# communication.net
KiCad netlist of a schematic drawn in Altium Designer
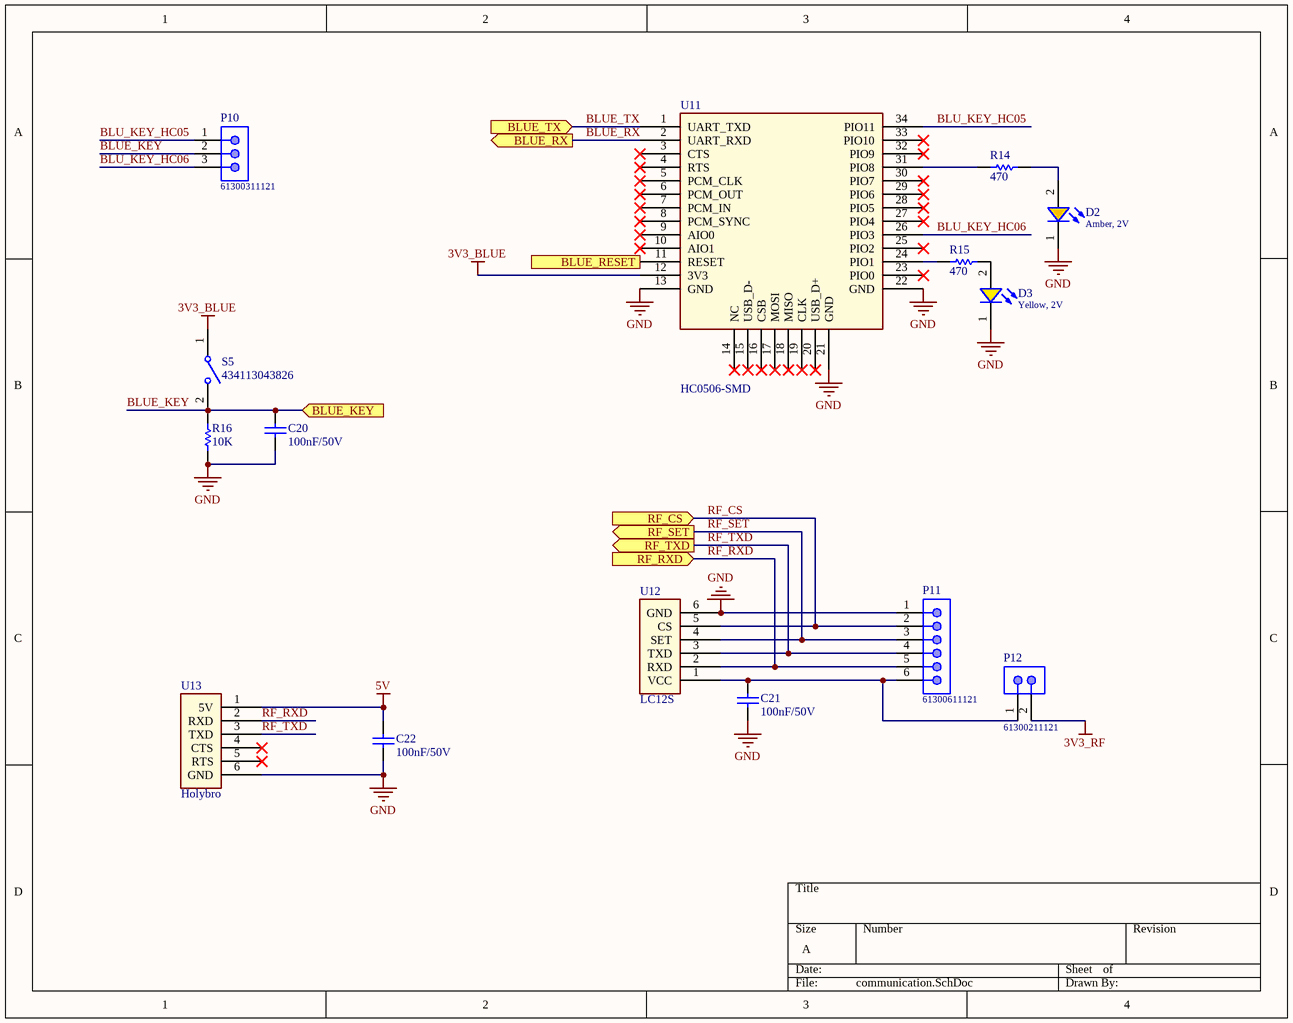
[diagram p0: communication.SchDoc]

(export (version "E")
  (design (tool "Eeschema 10.0.6"))
  (components
    (comp (ref "C20")
      (value "100nF/50V")
      (footprint "CAP-SM-0805")
      (description "CAP CER 0.1UF 50V Y5V 0805")
      (fields
        (field (name "MANUFACTURER") "Samsung Electro-Mechanics")
        (field (name "MANUFACTURER PART NUMBER") "CL21F104ZBCNNNC")
      )
      (libsource (lib "Capacitor") (part "Cap-100nF-50V-0805"))
    )
    (comp (ref "C21")
      (value "100nF/50V")
      (footprint "CAP-SM-0805")
      (description "CAP CER 0.1UF 50V Y5V 0805")
      (fields
        (field (name "MANUFACTURER") "Samsung Electro-Mechanics")
        (field (name "MANUFACTURER PART NUMBER") "CL21F104ZBCNNNC")
      )
      (libsource (lib "Capacitor") (part "Cap-100nF-50V-0805"))
    )
    (comp (ref "C22")
      (value "100nF/50V")
      (footprint "CAP-SM-0805")
      (description "CAP CER 0.1UF 50V Y5V 0805")
      (fields
        (field (name "MANUFACTURER") "Samsung Electro-Mechanics")
        (field (name "MANUFACTURER PART NUMBER") "CL21F104ZBCNNNC")
      )
      (libsource (lib "Capacitor") (part "Cap-100nF-50V-0805"))
    )
    (comp (ref "D2")
      (value "Amber, 2V")
      (footprint "WL-SMCW_0805")
      (description "WL-SMCW SMT Mono-color Chip LED Waterclear, size 0805, Amber, 2V, 140deg")
      (fields (field (name "PART NUMBER") "150080AS75000") (field (name "PUBLISHER") "Wurth Elektronik"))
      (libsource (lib "Chip_LEDs") (part "150080AS75000"))
    )
    (comp (ref "D3")
      (value "Yellow, 2V")
      (footprint "WL-SMCW_0805")
      (description "WL-SMCW SMT Mono-color Chip LED Waterclear, size 0805, Yellow, 2V, 140deg")
      (fields (field (name "PART NUMBER") "150080YS75000") (field (name "PUBLISHER") "Wurth Elektronik"))
      (libsource (lib "Chip_LEDs") (part "150080YS75000"))
    )
    (comp (ref "P10")
      (value "61300311121")
      (footprint "61300311121")
      (description "WR-PHD Pin Header, THT, pitch 2.54mm, Single Row, Vertical, 3p")
      (fields (field (name "MANUFACTURER") "Wurth Elektronik"))
      (libsource (lib "Pluggable_Connector") (part "61300311121"))
    )
    (comp (ref "P11")
      (value "61300611121")
      (footprint "61300611121")
      (description "WR-PHD Pin Header, THT, pitch 2.54mm, Single Row, Vertical, 6p")
      (fields (field (name "MANUFACTURER") "Wurth Elektronik"))
      (libsource (lib "Pluggable_Connector") (part "61300611121"))
    )
    (comp (ref "P12")
      (value "61300211121")
      (footprint "61300211121")
      (description "WR-PHD Pin Header, THT, pitch 2.54mm, Single Row, Vertical, 2p")
      (fields (field (name "MANUFACTURER") "Wurth Elektronik"))
      (libsource (lib "Pluggable_Connector") (part "61300211121"))
    )
    (comp (ref "R14")
      (value "470")
      (footprint "Resistor:RES-SM-0805")
      (description "RES 470 OHM JUMPER 0805")
      (fields
        (field (name "MANUFACTURER") "YAG6006CT-ND")
        (field (name "MANUFACTURER PART NUMBER") "PE0805FRF7W0R047L")
      )
      (libsource (lib "Resistor") (part "Res-470-0805"))
    )
    (comp (ref "R15")
      (value "470")
      (footprint "Resistor:RES-SM-0805")
      (description "RES 470 OHM JUMPER 0805")
      (fields
        (field (name "MANUFACTURER") "YAG6006CT-ND")
        (field (name "MANUFACTURER PART NUMBER") "PE0805FRF7W0R047L")
      )
      (libsource (lib "Resistor") (part "Res-470-0805"))
    )
    (comp (ref "R16")
      (value "10K")
      (footprint "Resistor:RES-SM-0805")
      (description "RES 10K OHM 1% 1/4W 0805")
      (fields
        (field (name "MANUFACTURER") "Stackpole Electronics Inc")
        (field (name "MANUFACTURER PART NUMBER") "RNCP0805FTD10K0")
      )
      (libsource (lib "Resistor") (part "Res-10k-0805"))
    )
    (comp (ref "S5")
      (value "434113043826")
      (footprint "434113043826")
      (description "WS-TASV J-Bend SMT Tact Switch 6x3.5mm, height 4.3mm, 260gf")
      (fields (field (name "PUBLISHER") "Wurth Elektronik"))
      (libsource (lib "Tact_Switches") (part "434113043826"))
    )
    (comp (ref "U11")
      (value "HC0506-SMD")
      (footprint "HC0506-SMD")
      (libsource (lib "Module") (part "HC0506-SMD"))
    )
    (comp (ref "U12")
      (value "LC12S")
      (footprint "LC12S")
      (fields (field (name "LOCAL SUPPLIER PART NUMBER") "HS000895"))
      (libsource (lib "Module") (part "LC12S"))
    )
    (comp (ref "U13") (value "Holybro") (footprint "Holybro") (libsource (lib "Module") (part "Holybro")))
  )
  (nets
    (net (code "1") (name "/BLUE_KEY") (class "Default")
      (node (ref "C20") (pin "2") (pinfunction "2_2") (pintype "passive"))
      (node (ref "P10") (pin "2") (pinfunction "2_2") (pintype "passive"))
      (node (ref "R16") (pin "1") (pinfunction "1_1") (pintype "passive"))
      (node (ref "S5") (pin "2") (pinfunction "2_2") (pintype "passive"))
    )
    (net (code "2") (name "/BLUE_RESET") (class "Default")
      (node (ref "U11") (pin "11") (pinfunction "RESET_11") (pintype "passive"))
    )
    (net (code "3") (name "/BLUE_RX") (class "Default")
      (node (ref "U11") (pin "2") (pinfunction "UART_RXD_2") (pintype "passive"))
    )
    (net (code "4") (name "/BLUE_TX") (class "Default")
      (node (ref "U11") (pin "1") (pinfunction "UART_TXD_1") (pintype "passive"))
    )
    (net (code "5") (name "/BLU_KEY_HC05") (class "Default")
      (node (ref "P10") (pin "1") (pinfunction "1_1") (pintype "passive"))
      (node (ref "U11") (pin "34") (pinfunction "PIO11_34") (pintype "passive"))
    )
    (net (code "6") (name "/BLU_KEY_HC06") (class "Default")
      (node (ref "P10") (pin "3") (pinfunction "3_3") (pintype "passive"))
      (node (ref "U11") (pin "26") (pinfunction "PIO3_26") (pintype "passive"))
    )
    (net (code "7") (name "/RF_CS") (class "Default")
      (node (ref "P11") (pin "2") (pinfunction "2_2") (pintype "passive"))
      (node (ref "U12") (pin "5") (pinfunction "CS_5") (pintype "passive"))
    )
    (net (code "8") (name "/RF_RXD") (class "Default")
      (node (ref "P11") (pin "5") (pinfunction "5_5") (pintype "passive"))
      (node (ref "U12") (pin "2") (pinfunction "RXD_2") (pintype "passive"))
      (node (ref "U13") (pin "2") (pinfunction "RXD_2") (pintype "passive"))
    )
    (net (code "9") (name "/RF_SET") (class "Default")
      (node (ref "P11") (pin "3") (pinfunction "3_3") (pintype "passive"))
      (node (ref "U12") (pin "4") (pinfunction "SET_4") (pintype "passive"))
    )
    (net (code "10") (name "/RF_TXD") (class "Default")
      (node (ref "P11") (pin "4") (pinfunction "4_4") (pintype "passive"))
      (node (ref "U12") (pin "3") (pinfunction "TXD_3") (pintype "passive"))
      (node (ref "U13") (pin "3") (pinfunction "TXD_3") (pintype "passive"))
    )
    (net (code "11") (name "3V3_BLUE") (class "Default")
      (node (ref "S5") (pin "1") (pinfunction "1_1") (pintype "passive"))
      (node (ref "U11") (pin "12") (pinfunction "3V3_12") (pintype "passive"))
    )
    (net (code "12") (name "3V3_RF") (class "Default")
      (node (ref "P12") (pin "2") (pinfunction "2_2") (pintype "passive"))
    )
    (net (code "13") (name "5V") (class "Default")
      (node (ref "C22") (pin "2") (pinfunction "2_2") (pintype "passive"))
      (node (ref "U13") (pin "1") (pinfunction "5V_1") (pintype "passive"))
    )
    (net (code "14") (name "GND") (class "Default")
      (node (ref "C20") (pin "1") (pinfunction "1_1") (pintype "passive"))
      (node (ref "C21") (pin "1") (pinfunction "1_1") (pintype "passive"))
      (node (ref "C22") (pin "1") (pinfunction "1_1") (pintype "passive"))
      (node (ref "D2") (pin "1") (pinfunction "K_1") (pintype "passive"))
      (node (ref "D3") (pin "1") (pinfunction "K_1") (pintype "passive"))
      (node (ref "P11") (pin "1") (pinfunction "1_1") (pintype "passive"))
      (node (ref "R16") (pin "2") (pinfunction "2_2") (pintype "passive"))
      (node (ref "U11") (pin "13") (pinfunction "GND_13") (pintype "passive"))
      (node (ref "U11") (pin "21") (pinfunction "GND_21") (pintype "passive"))
      (node (ref "U11") (pin "22") (pinfunction "GND_22") (pintype "passive"))
      (node (ref "U12") (pin "6") (pinfunction "GND_6") (pintype "passive"))
      (node (ref "U13") (pin "6") (pinfunction "GND_6") (pintype "passive"))
    )
    (net (code "15") (name "Net-(D2-A)") (class "Default")
      (node (ref "D2") (pin "2") (pinfunction "A_2") (pintype "passive"))
      (node (ref "R14") (pin "2") (pinfunction "2_2") (pintype "passive"))
    )
    (net (code "16") (name "Net-(D3-A)") (class "Default")
      (node (ref "D3") (pin "2") (pinfunction "A_2") (pintype "passive"))
      (node (ref "R15") (pin "2") (pinfunction "2_2") (pintype "passive"))
    )
    (net (code "17") (name "Net-(U11-PIO1)") (class "Default")
      (node (ref "R15") (pin "1") (pinfunction "1_1") (pintype "passive"))
      (node (ref "U11") (pin "24") (pinfunction "PIO1_24") (pintype "passive"))
    )
    (net (code "18") (name "Net-(U11-PIO8)") (class "Default")
      (node (ref "R14") (pin "1") (pinfunction "1_1") (pintype "passive"))
      (node (ref "U11") (pin "31") (pinfunction "PIO8_31") (pintype "passive"))
    )
    (net (code "19") (name "Net-(U12-VCC)") (class "Default")
      (node (ref "C21") (pin "2") (pinfunction "2_2") (pintype "passive"))
      (node (ref "P11") (pin "6") (pinfunction "6_6") (pintype "passive"))
      (node (ref "P12") (pin "1") (pinfunction "1_1") (pintype "passive"))
      (node (ref "U12") (pin "1") (pinfunction "VCC_1") (pintype "passive"))
    )
    (net (code "20") (name "unconnected-(U11-AIO0-Pad9)") (class "Default")
      (node (ref "U11") (pin "9") (pinfunction "AIO0_9") (pintype "passive+no_connect"))
    )
    (net (code "21") (name "unconnected-(U11-AIO1-Pad10)") (class "Default")
      (node (ref "U11") (pin "10") (pinfunction "AIO1_10") (pintype "passive+no_connect"))
    )
    (net (code "22") (name "unconnected-(U11-CLK-Pad19)") (class "Default")
      (node (ref "U11") (pin "19") (pinfunction "CLK_19") (pintype "passive+no_connect"))
    )
    (net (code "23") (name "unconnected-(U11-CSB-Pad16)") (class "Default")
      (node (ref "U11") (pin "16") (pinfunction "CSB_16") (pintype "passive+no_connect"))
    )
    (net (code "24") (name "unconnected-(U11-CTS-Pad3)") (class "Default")
      (node (ref "U11") (pin "3") (pinfunction "CTS_3") (pintype "passive+no_connect"))
    )
    (net (code "25") (name "unconnected-(U11-MISO-Pad18)") (class "Default")
      (node (ref "U11") (pin "18") (pinfunction "MISO_18") (pintype "passive+no_connect"))
    )
    (net (code "26") (name "unconnected-(U11-MOSI-Pad17)") (class "Default")
      (node (ref "U11") (pin "17") (pinfunction "MOSI_17") (pintype "passive+no_connect"))
    )
    (net (code "27") (name "unconnected-(U11-NC-Pad14)") (class "Default")
      (node (ref "U11") (pin "14") (pinfunction "NC_14") (pintype "passive+no_connect"))
    )
    (net (code "28") (name "unconnected-(U11-PCM_CLK-Pad5)") (class "Default")
      (node (ref "U11") (pin "5") (pinfunction "PCM_CLK_5") (pintype "passive+no_connect"))
    )
    (net (code "29") (name "unconnected-(U11-PCM_IN-Pad7)") (class "Default")
      (node (ref "U11") (pin "7") (pinfunction "PCM_IN_7") (pintype "passive+no_connect"))
    )
    (net (code "30") (name "unconnected-(U11-PCM_OUT-Pad6)") (class "Default")
      (node (ref "U11") (pin "6") (pinfunction "PCM_OUT_6") (pintype "passive+no_connect"))
    )
    (net (code "31") (name "unconnected-(U11-PCM_SYNC-Pad8)") (class "Default")
      (node (ref "U11") (pin "8") (pinfunction "PCM_SYNC_8") (pintype "passive+no_connect"))
    )
    (net (code "32") (name "unconnected-(U11-PIO0-Pad23)") (class "Default")
      (node (ref "U11") (pin "23") (pinfunction "PIO0_23") (pintype "passive+no_connect"))
    )
    (net (code "33") (name "unconnected-(U11-PIO2-Pad25)") (class "Default")
      (node (ref "U11") (pin "25") (pinfunction "PIO2_25") (pintype "passive+no_connect"))
    )
    (net (code "34") (name "unconnected-(U11-PIO4-Pad27)") (class "Default")
      (node (ref "U11") (pin "27") (pinfunction "PIO4_27") (pintype "passive+no_connect"))
    )
    (net (code "35") (name "unconnected-(U11-PIO5-Pad28)") (class "Default")
      (node (ref "U11") (pin "28") (pinfunction "PIO5_28") (pintype "passive+no_connect"))
    )
    (net (code "36") (name "unconnected-(U11-PIO6-Pad29)") (class "Default")
      (node (ref "U11") (pin "29") (pinfunction "PIO6_29") (pintype "passive+no_connect"))
    )
    (net (code "37") (name "unconnected-(U11-PIO7-Pad30)") (class "Default")
      (node (ref "U11") (pin "30") (pinfunction "PIO7_30") (pintype "passive+no_connect"))
    )
    (net (code "38") (name "unconnected-(U11-PIO9-Pad32)") (class "Default")
      (node (ref "U11") (pin "32") (pinfunction "PIO9_32") (pintype "passive+no_connect"))
    )
    (net (code "39") (name "unconnected-(U11-PIO10-Pad33)") (class "Default")
      (node (ref "U11") (pin "33") (pinfunction "PIO10_33") (pintype "passive+no_connect"))
    )
    (net (code "40") (name "unconnected-(U11-RTS-Pad4)") (class "Default")
      (node (ref "U11") (pin "4") (pinfunction "RTS_4") (pintype "passive+no_connect"))
    )
    (net (code "41") (name "unconnected-(U11-USB_D+-Pad20)") (class "Default")
      (node (ref "U11") (pin "20") (pinfunction "USB_D+_20") (pintype "passive+no_connect"))
    )
    (net (code "42") (name "unconnected-(U11-USB_D--Pad15)") (class "Default")
      (node (ref "U11") (pin "15") (pinfunction "USB_D-_15") (pintype "passive+no_connect"))
    )
    (net (code "43") (name "unconnected-(U13-CTS-Pad4)") (class "Default")
      (node (ref "U13") (pin "4") (pinfunction "CTS_4") (pintype "passive+no_connect"))
    )
    (net (code "44") (name "unconnected-(U13-RTS-Pad5)") (class "Default")
      (node (ref "U13") (pin "5") (pinfunction "RTS_5") (pintype "passive+no_connect"))
    )
  )
)
